# LED_Controler.net
KiCad netlist of a schematic drawn in Altium Designer
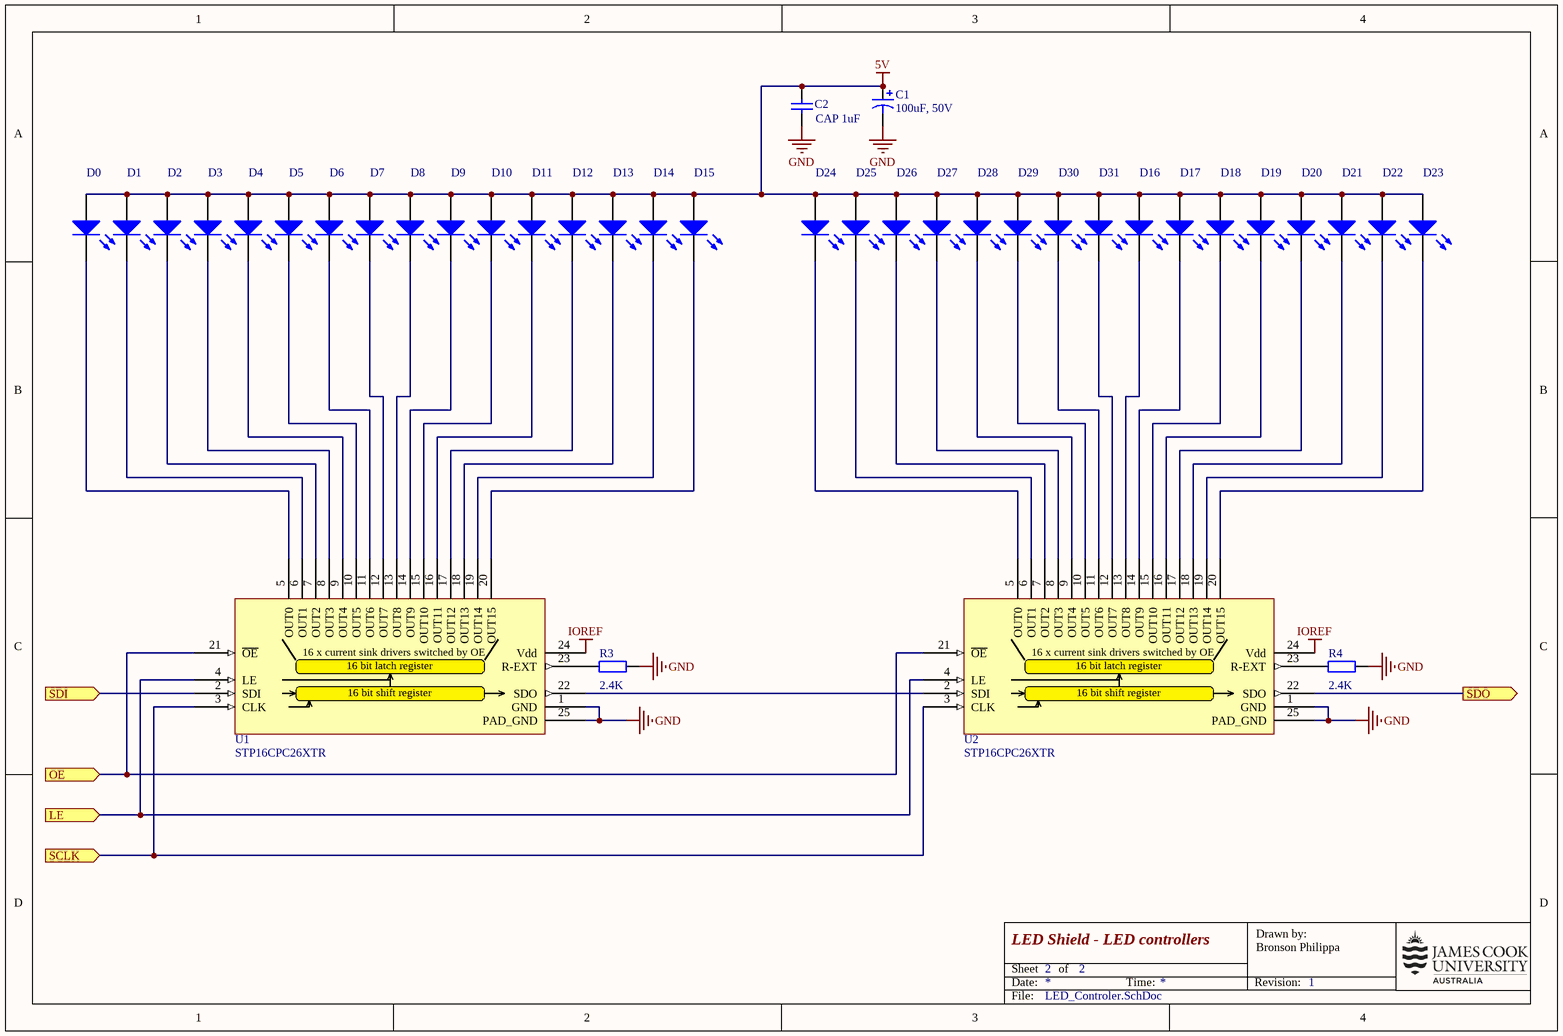
[diagram p0: LED_Controler.SchDoc]

(export (version "E")
  (design (tool "Eeschema 10.0.6"))
  (components
    (comp (ref "C1")
      (value "100uF, 50V")
      (footprint "Capacitor radial 8mm")
      (description "Electrolytic Capacitor, 100 µF, 50 V, ± 20%, Radial Leaded, 8 mm")
      (libsource (lib "JCULibrary") (part "Cap 100uF, 50V, THT radial"))
    )
    (comp (ref "C2")
      (value "CAP 1uF")
      (footprint "CAPC1206(3216)130_M")
      (description "CAP 1uF 25V ±10% 1206 (3216 Metric) Thickness 1.3mm SMD")
      (fields (field (name "TOLERANCE") "Â±10%"))
      (libsource (lib "Altium Content Vault") (part "CAP"))
    )
    (comp (ref "D0")
      (value "LED3")
      (footprint "3.5X2.8X1.9")
      (description "Typical BLUE SiC LED")
      (fields (field (name "PUBLISHER") "Altium Limited"))
      (libsource (lib "Miscellaneous Devices") (part "LED3"))
    )
    (comp (ref "D1")
      (value "LED3")
      (footprint "3.5X2.8X1.9")
      (description "Typical BLUE SiC LED")
      (fields (field (name "PUBLISHER") "Altium Limited"))
      (libsource (lib "Miscellaneous Devices") (part "LED3"))
    )
    (comp (ref "D2")
      (value "LED3")
      (footprint "3.5X2.8X1.9")
      (description "Typical BLUE SiC LED")
      (fields (field (name "PUBLISHER") "Altium Limited"))
      (libsource (lib "Miscellaneous Devices") (part "LED3"))
    )
    (comp (ref "D3")
      (value "LED3")
      (footprint "3.5X2.8X1.9")
      (description "Typical BLUE SiC LED")
      (fields (field (name "PUBLISHER") "Altium Limited"))
      (libsource (lib "Miscellaneous Devices") (part "LED3"))
    )
    (comp (ref "D4")
      (value "LED3")
      (footprint "3.5X2.8X1.9")
      (description "Typical BLUE SiC LED")
      (fields (field (name "PUBLISHER") "Altium Limited"))
      (libsource (lib "Miscellaneous Devices") (part "LED3"))
    )
    (comp (ref "D5")
      (value "LED3")
      (footprint "3.5X2.8X1.9")
      (description "Typical BLUE SiC LED")
      (fields (field (name "PUBLISHER") "Altium Limited"))
      (libsource (lib "Miscellaneous Devices") (part "LED3"))
    )
    (comp (ref "D6")
      (value "LED3")
      (footprint "3.5X2.8X1.9")
      (description "Typical BLUE SiC LED")
      (fields (field (name "PUBLISHER") "Altium Limited"))
      (libsource (lib "Miscellaneous Devices") (part "LED3"))
    )
    (comp (ref "D7")
      (value "LED3")
      (footprint "3.5X2.8X1.9")
      (description "Typical BLUE SiC LED")
      (fields (field (name "PUBLISHER") "Altium Limited"))
      (libsource (lib "Miscellaneous Devices") (part "LED3"))
    )
    (comp (ref "D8")
      (value "LED3")
      (footprint "3.5X2.8X1.9")
      (description "Typical BLUE SiC LED")
      (fields (field (name "PUBLISHER") "Altium Limited"))
      (libsource (lib "Miscellaneous Devices") (part "LED3"))
    )
    (comp (ref "D9")
      (value "LED3")
      (footprint "3.5X2.8X1.9")
      (description "Typical BLUE SiC LED")
      (fields (field (name "PUBLISHER") "Altium Limited"))
      (libsource (lib "Miscellaneous Devices") (part "LED3"))
    )
    (comp (ref "D10")
      (value "LED3")
      (footprint "3.5X2.8X1.9")
      (description "Typical BLUE SiC LED")
      (fields (field (name "PUBLISHER") "Altium Limited"))
      (libsource (lib "Miscellaneous Devices") (part "LED3"))
    )
    (comp (ref "D11")
      (value "LED3")
      (footprint "3.5X2.8X1.9")
      (description "Typical BLUE SiC LED")
      (fields (field (name "PUBLISHER") "Altium Limited"))
      (libsource (lib "Miscellaneous Devices") (part "LED3"))
    )
    (comp (ref "D12")
      (value "LED3")
      (footprint "3.5X2.8X1.9")
      (description "Typical BLUE SiC LED")
      (fields (field (name "PUBLISHER") "Altium Limited"))
      (libsource (lib "Miscellaneous Devices") (part "LED3"))
    )
    (comp (ref "D13")
      (value "LED3")
      (footprint "3.5X2.8X1.9")
      (description "Typical BLUE SiC LED")
      (fields (field (name "PUBLISHER") "Altium Limited"))
      (libsource (lib "Miscellaneous Devices") (part "LED3"))
    )
    (comp (ref "D14")
      (value "LED3")
      (footprint "3.5X2.8X1.9")
      (description "Typical BLUE SiC LED")
      (fields (field (name "PUBLISHER") "Altium Limited"))
      (libsource (lib "Miscellaneous Devices") (part "LED3"))
    )
    (comp (ref "D15")
      (value "LED3")
      (footprint "3.5X2.8X1.9")
      (description "Typical BLUE SiC LED")
      (fields (field (name "PUBLISHER") "Altium Limited"))
      (libsource (lib "Miscellaneous Devices") (part "LED3"))
    )
    (comp (ref "D16")
      (value "LED3")
      (footprint "3.5X2.8X1.9")
      (description "Typical BLUE SiC LED")
      (fields (field (name "PUBLISHER") "Altium Limited"))
      (libsource (lib "Miscellaneous Devices") (part "LED3"))
    )
    (comp (ref "D17")
      (value "LED3")
      (footprint "3.5X2.8X1.9")
      (description "Typical BLUE SiC LED")
      (fields (field (name "PUBLISHER") "Altium Limited"))
      (libsource (lib "Miscellaneous Devices") (part "LED3"))
    )
    (comp (ref "D18")
      (value "LED3")
      (footprint "3.5X2.8X1.9")
      (description "Typical BLUE SiC LED")
      (fields (field (name "PUBLISHER") "Altium Limited"))
      (libsource (lib "Miscellaneous Devices") (part "LED3"))
    )
    (comp (ref "D19")
      (value "LED3")
      (footprint "3.5X2.8X1.9")
      (description "Typical BLUE SiC LED")
      (fields (field (name "PUBLISHER") "Altium Limited"))
      (libsource (lib "Miscellaneous Devices") (part "LED3"))
    )
    (comp (ref "D20")
      (value "LED3")
      (footprint "3.5X2.8X1.9")
      (description "Typical BLUE SiC LED")
      (fields (field (name "PUBLISHER") "Altium Limited"))
      (libsource (lib "Miscellaneous Devices") (part "LED3"))
    )
    (comp (ref "D21")
      (value "LED3")
      (footprint "3.5X2.8X1.9")
      (description "Typical BLUE SiC LED")
      (fields (field (name "PUBLISHER") "Altium Limited"))
      (libsource (lib "Miscellaneous Devices") (part "LED3"))
    )
    (comp (ref "D22")
      (value "LED3")
      (footprint "3.5X2.8X1.9")
      (description "Typical BLUE SiC LED")
      (fields (field (name "PUBLISHER") "Altium Limited"))
      (libsource (lib "Miscellaneous Devices") (part "LED3"))
    )
    (comp (ref "D23")
      (value "LED3")
      (footprint "3.5X2.8X1.9")
      (description "Typical BLUE SiC LED")
      (fields (field (name "PUBLISHER") "Altium Limited"))
      (libsource (lib "Miscellaneous Devices") (part "LED3"))
    )
    (comp (ref "D24")
      (value "LED3")
      (footprint "3.5X2.8X1.9")
      (description "Typical BLUE SiC LED")
      (fields (field (name "PUBLISHER") "Altium Limited"))
      (libsource (lib "Miscellaneous Devices") (part "LED3"))
    )
    (comp (ref "D25")
      (value "LED3")
      (footprint "3.5X2.8X1.9")
      (description "Typical BLUE SiC LED")
      (fields (field (name "PUBLISHER") "Altium Limited"))
      (libsource (lib "Miscellaneous Devices") (part "LED3"))
    )
    (comp (ref "D26")
      (value "LED3")
      (footprint "3.5X2.8X1.9")
      (description "Typical BLUE SiC LED")
      (fields (field (name "PUBLISHER") "Altium Limited"))
      (libsource (lib "Miscellaneous Devices") (part "LED3"))
    )
    (comp (ref "D27")
      (value "LED3")
      (footprint "3.5X2.8X1.9")
      (description "Typical BLUE SiC LED")
      (fields (field (name "PUBLISHER") "Altium Limited"))
      (libsource (lib "Miscellaneous Devices") (part "LED3"))
    )
    (comp (ref "D28")
      (value "LED3")
      (footprint "3.5X2.8X1.9")
      (description "Typical BLUE SiC LED")
      (fields (field (name "PUBLISHER") "Altium Limited"))
      (libsource (lib "Miscellaneous Devices") (part "LED3"))
    )
    (comp (ref "D29")
      (value "LED3")
      (footprint "3.5X2.8X1.9")
      (description "Typical BLUE SiC LED")
      (fields (field (name "PUBLISHER") "Altium Limited"))
      (libsource (lib "Miscellaneous Devices") (part "LED3"))
    )
    (comp (ref "D30")
      (value "LED3")
      (footprint "3.5X2.8X1.9")
      (description "Typical BLUE SiC LED")
      (fields (field (name "PUBLISHER") "Altium Limited"))
      (libsource (lib "Miscellaneous Devices") (part "LED3"))
    )
    (comp (ref "D31")
      (value "LED3")
      (footprint "3.5X2.8X1.9")
      (description "Typical BLUE SiC LED")
      (fields (field (name "PUBLISHER") "Altium Limited"))
      (libsource (lib "Miscellaneous Devices") (part "LED3"))
    )
    (comp (ref "R3")
      (value "2.4K")
      (footprint "AXIAL-0.4")
      (description "Resistor")
      (fields (field (name "Comment") "Res2") (field (name "PUBLISHER") "Altium Limited"))
      (libsource (lib "Miscellaneous Devices") (part "Res2"))
    )
    (comp (ref "R4")
      (value "2.4K")
      (footprint "AXIAL-0.4")
      (description "Resistor")
      (fields (field (name "Comment") "Res2") (field (name "PUBLISHER") "Altium Limited"))
      (libsource (lib "Miscellaneous Devices") (part "Res2"))
    )
    (comp (ref "U1")
      (value "STP16CPC26XTR")
      (footprint "STP16CPC26XTR TSSOP-24")
      (description "ST Microelectronics STP16CPC26XTR constant current LED sink driver")
      (libsource (lib "JCULibrary") (part "LED sink driver 16 ch STP16CPC26XTR"))
    )
    (comp (ref "U2")
      (value "STP16CPC26XTR")
      (footprint "STP16CPC26XTR TSSOP-24")
      (description "ST Microelectronics STP16CPC26XTR constant current LED sink driver")
      (libsource (lib "JCULibrary") (part "LED sink driver 16 ch STP16CPC26XTR"))
    )
  )
  (nets
    (net (code "1") (name "/LE") (class "Default")
      (node (ref "U1") (pin "4") (pinfunction "LE_4") (pintype "input"))
      (node (ref "U2") (pin "4") (pinfunction "LE_4") (pintype "input"))
    )
    (net (code "2") (name "/OE") (class "Default")
      (node (ref "U1") (pin "21") (pinfunction "~{OE}_21") (pintype "input"))
      (node (ref "U2") (pin "21") (pinfunction "~{OE}_21") (pintype "input"))
    )
    (net (code "3") (name "/SCLK") (class "Default")
      (node (ref "U1") (pin "3") (pinfunction "CLK_3") (pintype "input"))
      (node (ref "U2") (pin "3") (pinfunction "CLK_3") (pintype "input"))
    )
    (net (code "4") (name "/SDI") (class "Default")
      (node (ref "U1") (pin "2") (pinfunction "SDI_2") (pintype "input"))
    )
    (net (code "5") (name "/SDO") (class "Default")
      (node (ref "U2") (pin "22") (pinfunction "SDO_22") (pintype "output"))
    )
    (net (code "6") (name "5V") (class "Default")
      (node (ref "C1") (pin "1") (pinfunction "1_1") (pintype "passive"))
      (node (ref "C2") (pin "1") (pinfunction "1_1") (pintype "passive"))
      (node (ref "D0") (pin "1") (pinfunction "A_1") (pintype "passive"))
      (node (ref "D1") (pin "1") (pinfunction "A_1") (pintype "passive"))
      (node (ref "D10") (pin "1") (pinfunction "A_1") (pintype "passive"))
      (node (ref "D11") (pin "1") (pinfunction "A_1") (pintype "passive"))
      (node (ref "D12") (pin "1") (pinfunction "A_1") (pintype "passive"))
      (node (ref "D13") (pin "1") (pinfunction "A_1") (pintype "passive"))
      (node (ref "D14") (pin "1") (pinfunction "A_1") (pintype "passive"))
      (node (ref "D15") (pin "1") (pinfunction "A_1") (pintype "passive"))
      (node (ref "D16") (pin "1") (pinfunction "A_1") (pintype "passive"))
      (node (ref "D17") (pin "1") (pinfunction "A_1") (pintype "passive"))
      (node (ref "D18") (pin "1") (pinfunction "A_1") (pintype "passive"))
      (node (ref "D19") (pin "1") (pinfunction "A_1") (pintype "passive"))
      (node (ref "D2") (pin "1") (pinfunction "A_1") (pintype "passive"))
      (node (ref "D20") (pin "1") (pinfunction "A_1") (pintype "passive"))
      (node (ref "D21") (pin "1") (pinfunction "A_1") (pintype "passive"))
      (node (ref "D22") (pin "1") (pinfunction "A_1") (pintype "passive"))
      (node (ref "D23") (pin "1") (pinfunction "A_1") (pintype "passive"))
      (node (ref "D24") (pin "1") (pinfunction "A_1") (pintype "passive"))
      (node (ref "D25") (pin "1") (pinfunction "A_1") (pintype "passive"))
      (node (ref "D26") (pin "1") (pinfunction "A_1") (pintype "passive"))
      (node (ref "D27") (pin "1") (pinfunction "A_1") (pintype "passive"))
      (node (ref "D28") (pin "1") (pinfunction "A_1") (pintype "passive"))
      (node (ref "D29") (pin "1") (pinfunction "A_1") (pintype "passive"))
      (node (ref "D3") (pin "1") (pinfunction "A_1") (pintype "passive"))
      (node (ref "D30") (pin "1") (pinfunction "A_1") (pintype "passive"))
      (node (ref "D31") (pin "1") (pinfunction "A_1") (pintype "passive"))
      (node (ref "D4") (pin "1") (pinfunction "A_1") (pintype "passive"))
      (node (ref "D5") (pin "1") (pinfunction "A_1") (pintype "passive"))
      (node (ref "D6") (pin "1") (pinfunction "A_1") (pintype "passive"))
      (node (ref "D7") (pin "1") (pinfunction "A_1") (pintype "passive"))
      (node (ref "D8") (pin "1") (pinfunction "A_1") (pintype "passive"))
      (node (ref "D9") (pin "1") (pinfunction "A_1") (pintype "passive"))
    )
    (net (code "7") (name "GND") (class "Default")
      (node (ref "C1") (pin "2") (pinfunction "2_2") (pintype "passive"))
      (node (ref "C2") (pin "2") (pinfunction "2_2") (pintype "passive"))
      (node (ref "R3") (pin "2") (pinfunction "2_2") (pintype "passive"))
      (node (ref "R4") (pin "2") (pinfunction "2_2") (pintype "passive"))
      (node (ref "U1") (pin "1") (pinfunction "GND_1") (pintype "power_in"))
      (node (ref "U1") (pin "25") (pinfunction "PAD_GND_25") (pintype "power_in"))
      (node (ref "U2") (pin "1") (pinfunction "GND_1") (pintype "power_in"))
      (node (ref "U2") (pin "25") (pinfunction "PAD_GND_25") (pintype "power_in"))
    )
    (net (code "8") (name "IOREF") (class "Default")
      (node (ref "U1") (pin "24") (pinfunction "Vdd_24") (pintype "power_in"))
      (node (ref "U2") (pin "24") (pinfunction "Vdd_24") (pintype "power_in"))
    )
    (net (code "9") (name "Net-(D0-K)") (class "Default")
      (node (ref "D0") (pin "2") (pinfunction "K_2") (pintype "passive"))
      (node (ref "U1") (pin "5") (pinfunction "OUT0_5") (pintype "power_in"))
    )
    (net (code "10") (name "Net-(D1-K)") (class "Default")
      (node (ref "D1") (pin "2") (pinfunction "K_2") (pintype "passive"))
      (node (ref "U1") (pin "6") (pinfunction "OUT1_6") (pintype "power_in"))
    )
    (net (code "11") (name "Net-(D2-K)") (class "Default")
      (node (ref "D2") (pin "2") (pinfunction "K_2") (pintype "passive"))
      (node (ref "U1") (pin "7") (pinfunction "OUT2_7") (pintype "power_in"))
    )
    (net (code "12") (name "Net-(D3-K)") (class "Default")
      (node (ref "D3") (pin "2") (pinfunction "K_2") (pintype "passive"))
      (node (ref "U1") (pin "8") (pinfunction "OUT3_8") (pintype "power_in"))
    )
    (net (code "13") (name "Net-(D4-K)") (class "Default")
      (node (ref "D4") (pin "2") (pinfunction "K_2") (pintype "passive"))
      (node (ref "U1") (pin "9") (pinfunction "OUT4_9") (pintype "power_in"))
    )
    (net (code "14") (name "Net-(D5-K)") (class "Default")
      (node (ref "D5") (pin "2") (pinfunction "K_2") (pintype "passive"))
      (node (ref "U1") (pin "10") (pinfunction "OUT5_10") (pintype "power_in"))
    )
    (net (code "15") (name "Net-(D6-K)") (class "Default")
      (node (ref "D6") (pin "2") (pinfunction "K_2") (pintype "passive"))
      (node (ref "U1") (pin "11") (pinfunction "OUT6_11") (pintype "power_in"))
    )
    (net (code "16") (name "Net-(D7-K)") (class "Default")
      (node (ref "D7") (pin "2") (pinfunction "K_2") (pintype "passive"))
      (node (ref "U1") (pin "12") (pinfunction "OUT7_12") (pintype "power_in"))
    )
    (net (code "17") (name "Net-(D8-K)") (class "Default")
      (node (ref "D8") (pin "2") (pinfunction "K_2") (pintype "passive"))
      (node (ref "U1") (pin "13") (pinfunction "OUT8_13") (pintype "power_in"))
    )
    (net (code "18") (name "Net-(D9-K)") (class "Default")
      (node (ref "D9") (pin "2") (pinfunction "K_2") (pintype "passive"))
      (node (ref "U1") (pin "14") (pinfunction "OUT9_14") (pintype "power_in"))
    )
    (net (code "19") (name "Net-(D10-K)") (class "Default")
      (node (ref "D10") (pin "2") (pinfunction "K_2") (pintype "passive"))
      (node (ref "U1") (pin "15") (pinfunction "OUT10_15") (pintype "power_in"))
    )
    (net (code "20") (name "Net-(D11-K)") (class "Default")
      (node (ref "D11") (pin "2") (pinfunction "K_2") (pintype "passive"))
      (node (ref "U1") (pin "16") (pinfunction "OUT11_16") (pintype "power_in"))
    )
    (net (code "21") (name "Net-(D12-K)") (class "Default")
      (node (ref "D12") (pin "2") (pinfunction "K_2") (pintype "passive"))
      (node (ref "U1") (pin "17") (pinfunction "OUT12_17") (pintype "power_in"))
    )
    (net (code "22") (name "Net-(D13-K)") (class "Default")
      (node (ref "D13") (pin "2") (pinfunction "K_2") (pintype "passive"))
      (node (ref "U1") (pin "18") (pinfunction "OUT13_18") (pintype "power_in"))
    )
    (net (code "23") (name "Net-(D14-K)") (class "Default")
      (node (ref "D14") (pin "2") (pinfunction "K_2") (pintype "passive"))
      (node (ref "U1") (pin "19") (pinfunction "OUT14_19") (pintype "power_in"))
    )
    (net (code "24") (name "Net-(D15-K)") (class "Default")
      (node (ref "D15") (pin "2") (pinfunction "K_2") (pintype "passive"))
      (node (ref "U1") (pin "20") (pinfunction "OUT15_20") (pintype "power_in"))
    )
    (net (code "25") (name "Net-(D16-K)") (class "Default")
      (node (ref "D16") (pin "2") (pinfunction "K_2") (pintype "passive"))
      (node (ref "U2") (pin "13") (pinfunction "OUT8_13") (pintype "power_in"))
    )
    (net (code "26") (name "Net-(D17-K)") (class "Default")
      (node (ref "D17") (pin "2") (pinfunction "K_2") (pintype "passive"))
      (node (ref "U2") (pin "14") (pinfunction "OUT9_14") (pintype "power_in"))
    )
    (net (code "27") (name "Net-(D18-K)") (class "Default")
      (node (ref "D18") (pin "2") (pinfunction "K_2") (pintype "passive"))
      (node (ref "U2") (pin "15") (pinfunction "OUT10_15") (pintype "power_in"))
    )
    (net (code "28") (name "Net-(D19-K)") (class "Default")
      (node (ref "D19") (pin "2") (pinfunction "K_2") (pintype "passive"))
      (node (ref "U2") (pin "16") (pinfunction "OUT11_16") (pintype "power_in"))
    )
    (net (code "29") (name "Net-(D20-K)") (class "Default")
      (node (ref "D20") (pin "2") (pinfunction "K_2") (pintype "passive"))
      (node (ref "U2") (pin "17") (pinfunction "OUT12_17") (pintype "power_in"))
    )
    (net (code "30") (name "Net-(D21-K)") (class "Default")
      (node (ref "D21") (pin "2") (pinfunction "K_2") (pintype "passive"))
      (node (ref "U2") (pin "18") (pinfunction "OUT13_18") (pintype "power_in"))
    )
    (net (code "31") (name "Net-(D22-K)") (class "Default")
      (node (ref "D22") (pin "2") (pinfunction "K_2") (pintype "passive"))
      (node (ref "U2") (pin "19") (pinfunction "OUT14_19") (pintype "power_in"))
    )
    (net (code "32") (name "Net-(D23-K)") (class "Default")
      (node (ref "D23") (pin "2") (pinfunction "K_2") (pintype "passive"))
      (node (ref "U2") (pin "20") (pinfunction "OUT15_20") (pintype "power_in"))
    )
    (net (code "33") (name "Net-(D24-K)") (class "Default")
      (node (ref "D24") (pin "2") (pinfunction "K_2") (pintype "passive"))
      (node (ref "U2") (pin "5") (pinfunction "OUT0_5") (pintype "power_in"))
    )
    (net (code "34") (name "Net-(D25-K)") (class "Default")
      (node (ref "D25") (pin "2") (pinfunction "K_2") (pintype "passive"))
      (node (ref "U2") (pin "6") (pinfunction "OUT1_6") (pintype "power_in"))
    )
    (net (code "35") (name "Net-(D26-K)") (class "Default")
      (node (ref "D26") (pin "2") (pinfunction "K_2") (pintype "passive"))
      (node (ref "U2") (pin "7") (pinfunction "OUT2_7") (pintype "power_in"))
    )
    (net (code "36") (name "Net-(D27-K)") (class "Default")
      (node (ref "D27") (pin "2") (pinfunction "K_2") (pintype "passive"))
      (node (ref "U2") (pin "8") (pinfunction "OUT3_8") (pintype "power_in"))
    )
    (net (code "37") (name "Net-(D28-K)") (class "Default")
      (node (ref "D28") (pin "2") (pinfunction "K_2") (pintype "passive"))
      (node (ref "U2") (pin "9") (pinfunction "OUT4_9") (pintype "power_in"))
    )
    (net (code "38") (name "Net-(D29-K)") (class "Default")
      (node (ref "D29") (pin "2") (pinfunction "K_2") (pintype "passive"))
      (node (ref "U2") (pin "10") (pinfunction "OUT5_10") (pintype "power_in"))
    )
    (net (code "39") (name "Net-(D30-K)") (class "Default")
      (node (ref "D30") (pin "2") (pinfunction "K_2") (pintype "passive"))
      (node (ref "U2") (pin "11") (pinfunction "OUT6_11") (pintype "power_in"))
    )
    (net (code "40") (name "Net-(D31-K)") (class "Default")
      (node (ref "D31") (pin "2") (pinfunction "K_2") (pintype "passive"))
      (node (ref "U2") (pin "12") (pinfunction "OUT7_12") (pintype "power_in"))
    )
    (net (code "41") (name "Net-(U1-R-EXT)") (class "Default")
      (node (ref "R3") (pin "1") (pinfunction "1_1") (pintype "passive"))
      (node (ref "U1") (pin "23") (pinfunction "R-EXT_23") (pintype "output"))
    )
    (net (code "42") (name "Net-(U1-SDO)") (class "Default")
      (node (ref "U1") (pin "22") (pinfunction "SDO_22") (pintype "output"))
      (node (ref "U2") (pin "2") (pinfunction "SDI_2") (pintype "input"))
    )
    (net (code "43") (name "Net-(U2-R-EXT)") (class "Default")
      (node (ref "R4") (pin "1") (pinfunction "1_1") (pintype "passive"))
      (node (ref "U2") (pin "23") (pinfunction "R-EXT_23") (pintype "output"))
    )
  )
)
